# xe.net
KiCad netlist of a schematic drawn in Altium Designer
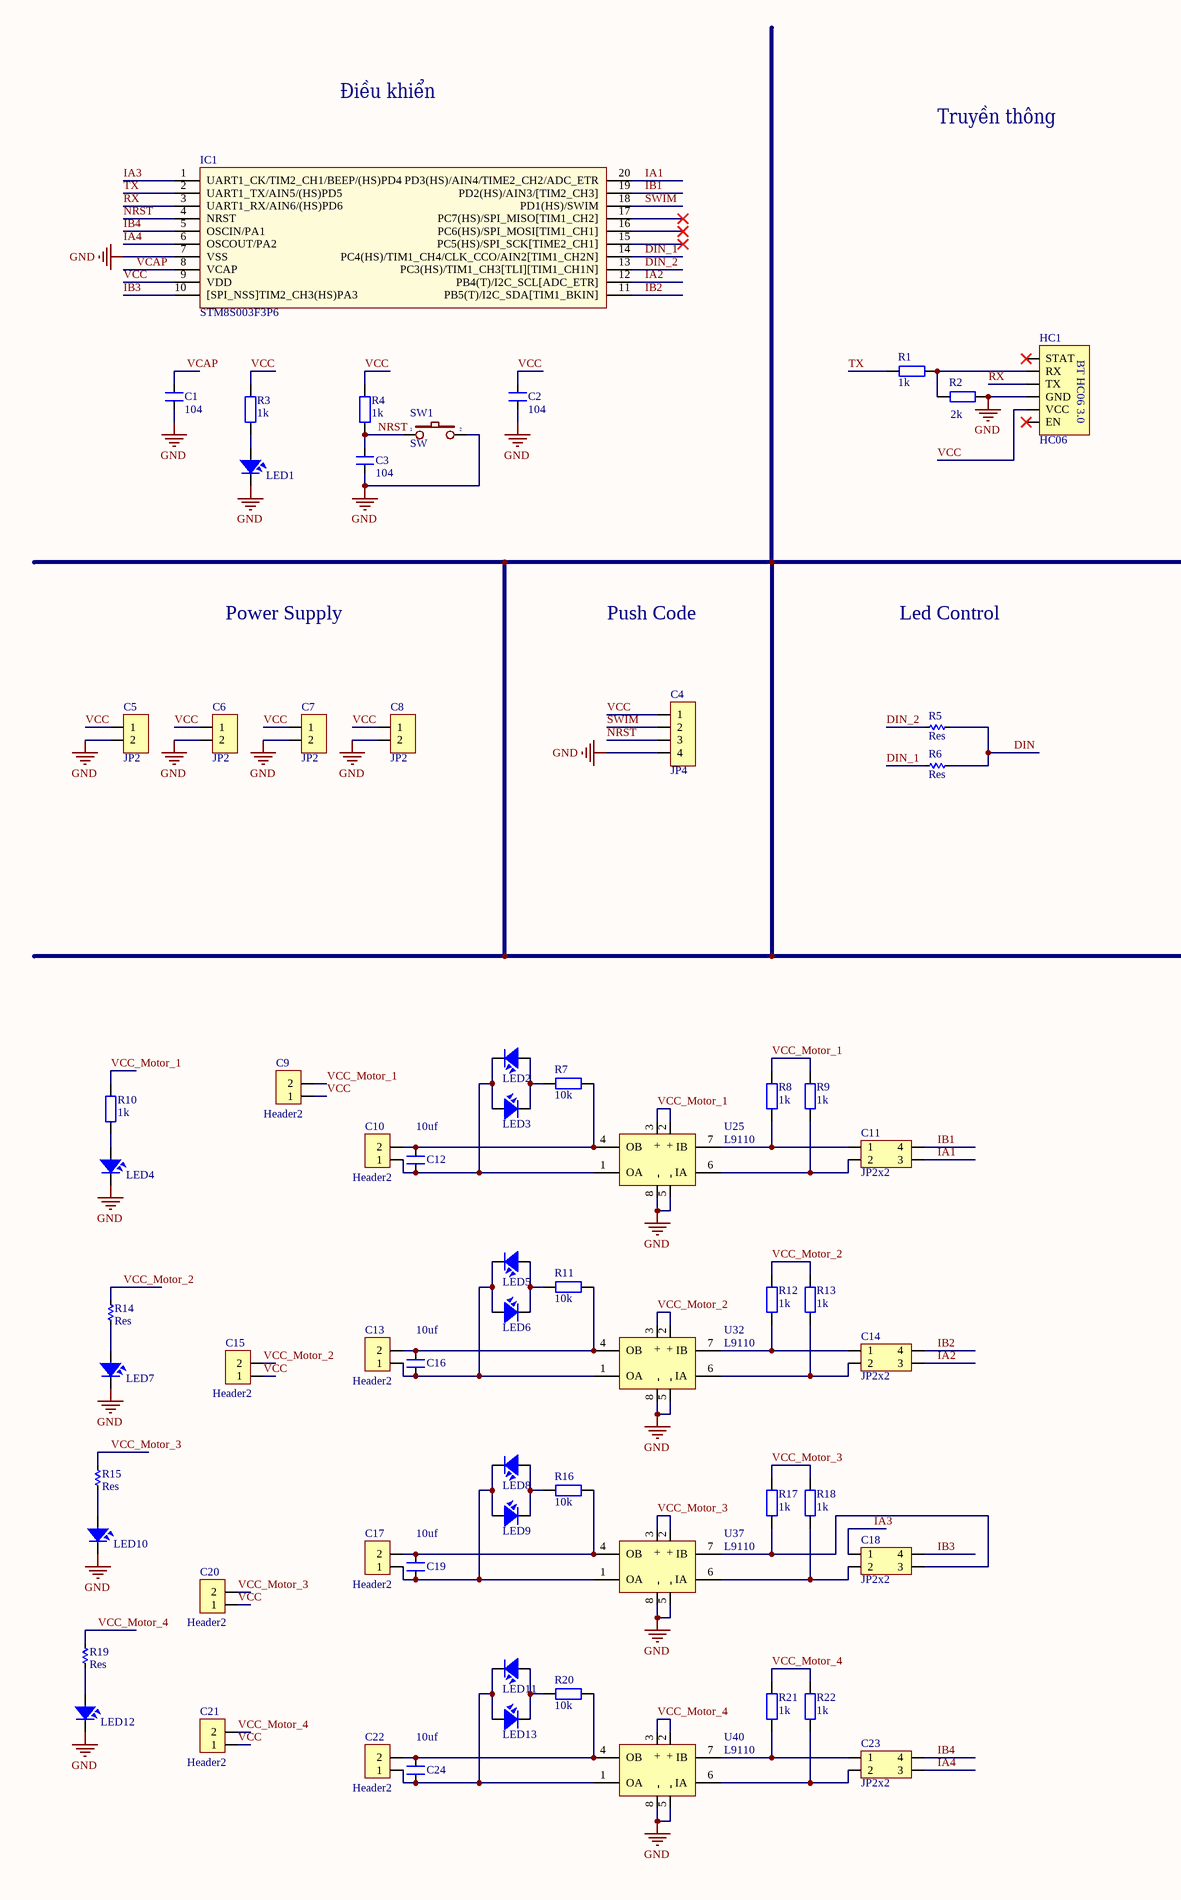
[diagram p0: xe.SchDoc, left]
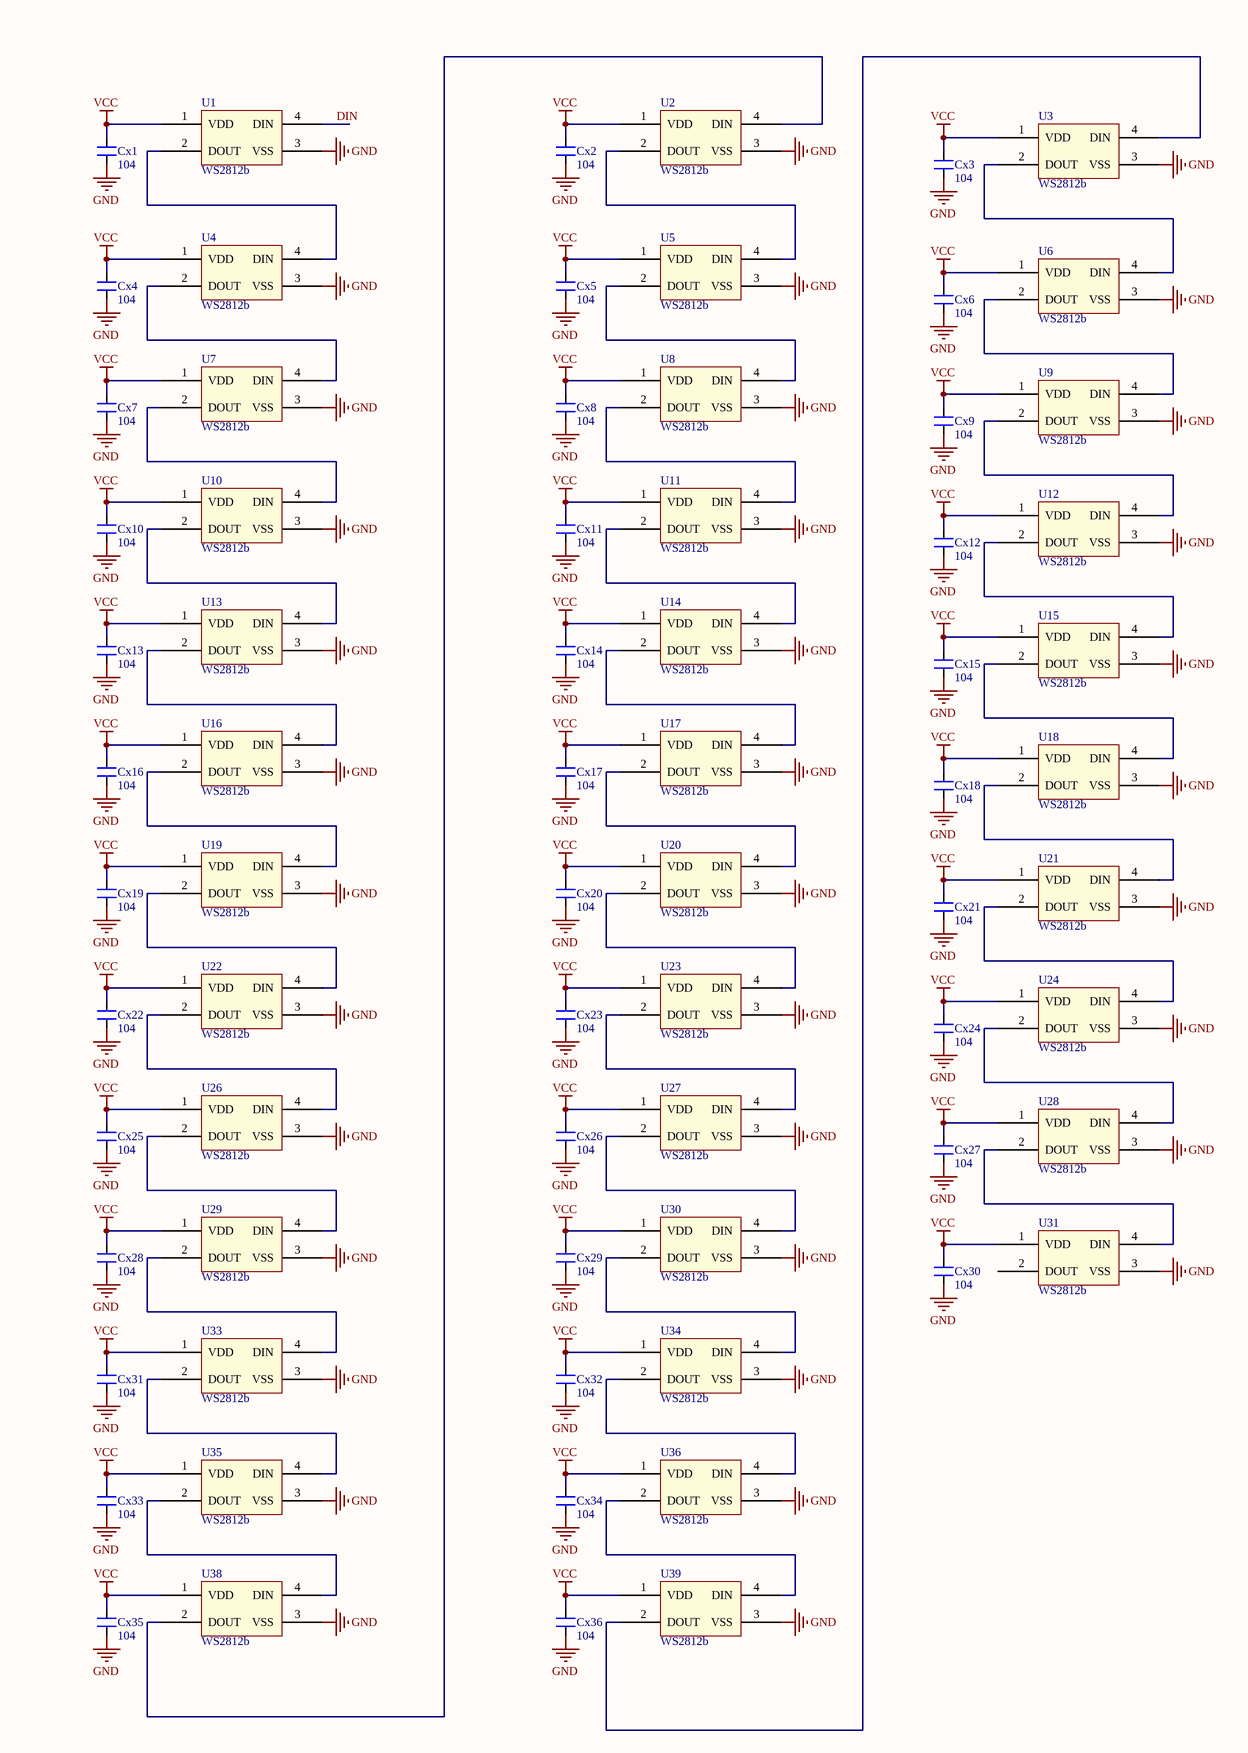
[diagram p1: xe.SchDoc, right]

(export (version "E")
  (design (tool "Eeschema 10.0.6"))
  (components
    (comp (ref "C1")
      (value "104")
      (footprint "SM-CAP-0805")
      (fields (field (name "DESIGNED BY") "VanDungEvn"))
      (libsource (lib "syhaunguyen") (part "CN"))
    )
    (comp (ref "C2")
      (value "104")
      (footprint "SM-CAP-0805")
      (fields (field (name "DESIGNED BY") "VanDungEvn"))
      (libsource (lib "syhaunguyen") (part "CN"))
    )
    (comp (ref "C3")
      (value "104")
      (footprint "SM-CAP-0805")
      (fields (field (name "DESIGNED BY") "VanDungEvn"))
      (libsource (lib "syhaunguyen") (part "CN"))
    )
    (comp (ref "C4")
      (value "JP4")
      (footprint "JP4-D1C")
      (description "WR-PHD 2.54 mm Angled Socket Header")
      (fields
        (field (name "MANUFACTURER") "Würth Elektronik eiSos GmbH")
        (field (name "PARTNO") "613004143121")
        (field (name "CREATED BY") "Karrer Zheng")
      )
      (libsource (lib "LIBRARY") (part "JP4"))
    )
    (comp (ref "C5")
      (value "JP2")
      (footprint "JP2-C1T")
      (description "WR-PHD 2.54 mm Angled Socket Header")
      (fields
        (field (name "MANUFACTURER") "Würth Elektronik eiSos GmbH")
        (field (name "PARTNO") "613002143121")
        (field (name "CREATED BY") "Karrer Zheng")
      )
      (libsource (lib "LIBRARY") (part "JP2"))
    )
    (comp (ref "C6")
      (value "JP2")
      (footprint "JP2-C1T")
      (description "WR-PHD 2.54 mm Angled Socket Header")
      (fields
        (field (name "MANUFACTURER") "Würth Elektronik eiSos GmbH")
        (field (name "PARTNO") "613002143121")
        (field (name "CREATED BY") "Karrer Zheng")
      )
      (libsource (lib "LIBRARY") (part "JP2"))
    )
    (comp (ref "C7")
      (value "JP2")
      (footprint "JP2-C1T")
      (description "WR-PHD 2.54 mm Angled Socket Header")
      (fields
        (field (name "MANUFACTURER") "Würth Elektronik eiSos GmbH")
        (field (name "PARTNO") "613002143121")
        (field (name "CREATED BY") "Karrer Zheng")
      )
      (libsource (lib "LIBRARY") (part "JP2"))
    )
    (comp (ref "C8")
      (value "JP2")
      (footprint "JP2-C1T")
      (description "WR-PHD 2.54 mm Angled Socket Header")
      (fields
        (field (name "MANUFACTURER") "Würth Elektronik eiSos GmbH")
        (field (name "PARTNO") "613002143121")
        (field (name "CREATED BY") "Karrer Zheng")
      )
      (libsource (lib "LIBRARY") (part "JP2"))
    )
    (comp (ref "C9")
      (value "Header2")
      (footprint "Header2")
      (description "Header IDC, 2 x 1 Pin Vertical 2.54mm Pitch (Non-Boxed, Male)")
      (fields
        (field (name "MANUFACTURER") "Würth Elektronik eiSos GmbH")
        (field (name "PARTNO") "613002143121")
        (field (name "CREATED BY") "Karrer Zheng")
      )
      (libsource (lib "LIBRARY") (part "Header2"))
    )
    (comp (ref "C10")
      (value "Header2")
      (footprint "Header2")
      (description "Header IDC, 2 x 1 Pin Vertical 2.54mm Pitch (Non-Boxed, Male)")
      (fields
        (field (name "MANUFACTURER") "Würth Elektronik eiSos GmbH")
        (field (name "PARTNO") "613002143121")
        (field (name "CREATED BY") "Karrer Zheng")
      )
      (libsource (lib "LIBRARY") (part "Header2"))
    )
    (comp (ref "C11")
      (value "JP2x2")
      (footprint "JP2-D2T")
      (description "WR-PHD 2.54 mm Dual Socket Header")
      (fields
        (field (name "MANUFACTURER") "Würth Elektronik eiSos GmbH")
        (field (name "PARTNO") "61300421821")
        (field (name "CREATED BY") "Karrer Zheng")
      )
      (libsource (lib "LIBRARY") (part "JP2x2"))
    )
    (comp (ref "C12")
      (value "10uf")
      (footprint "SM-CAP-0805")
      (fields (field (name "DESIGNED BY") "VanDungEvn"))
      (libsource (lib "syhaunguyen") (part "CN"))
    )
    (comp (ref "C13")
      (value "Header2")
      (footprint "Header2")
      (description "Header IDC, 2 x 1 Pin Vertical 2.54mm Pitch (Non-Boxed, Male)")
      (fields
        (field (name "MANUFACTURER") "Würth Elektronik eiSos GmbH")
        (field (name "PARTNO") "613002143121")
        (field (name "CREATED BY") "Karrer Zheng")
      )
      (libsource (lib "LIBRARY") (part "Header2"))
    )
    (comp (ref "C14")
      (value "JP2x2")
      (footprint "JP2-D2T")
      (description "WR-PHD 2.54 mm Dual Socket Header")
      (fields
        (field (name "MANUFACTURER") "Würth Elektronik eiSos GmbH")
        (field (name "PARTNO") "61300421821")
        (field (name "CREATED BY") "Karrer Zheng")
      )
      (libsource (lib "LIBRARY") (part "JP2x2"))
    )
    (comp (ref "C15")
      (value "Header2")
      (footprint "Header2")
      (description "Header IDC, 2 x 1 Pin Vertical 2.54mm Pitch (Non-Boxed, Male)")
      (fields
        (field (name "MANUFACTURER") "Würth Elektronik eiSos GmbH")
        (field (name "PARTNO") "613002143121")
        (field (name "CREATED BY") "Karrer Zheng")
      )
      (libsource (lib "LIBRARY") (part "Header2"))
    )
    (comp (ref "C16")
      (value "10uf")
      (footprint "SM-CAP-0805")
      (fields (field (name "DESIGNED BY") "VanDungEvn"))
      (libsource (lib "syhaunguyen") (part "CN"))
    )
    (comp (ref "C17")
      (value "Header2")
      (footprint "Header2")
      (description "Header IDC, 2 x 1 Pin Vertical 2.54mm Pitch (Non-Boxed, Male)")
      (fields
        (field (name "MANUFACTURER") "Würth Elektronik eiSos GmbH")
        (field (name "PARTNO") "613002143121")
        (field (name "CREATED BY") "Karrer Zheng")
      )
      (libsource (lib "LIBRARY") (part "Header2"))
    )
    (comp (ref "C18")
      (value "JP2x2")
      (footprint "JP2-D2T")
      (description "WR-PHD 2.54 mm Dual Socket Header")
      (fields
        (field (name "MANUFACTURER") "Würth Elektronik eiSos GmbH")
        (field (name "PARTNO") "61300421821")
        (field (name "CREATED BY") "Karrer Zheng")
      )
      (libsource (lib "LIBRARY") (part "JP2x2"))
    )
    (comp (ref "C19")
      (value "10uf")
      (footprint "SM-CAP-0805")
      (fields (field (name "DESIGNED BY") "VanDungEvn"))
      (libsource (lib "syhaunguyen") (part "CN"))
    )
    (comp (ref "C20")
      (value "Header2")
      (footprint "Header2")
      (description "Header IDC, 2 x 1 Pin Vertical 2.54mm Pitch (Non-Boxed, Male)")
      (fields
        (field (name "MANUFACTURER") "Würth Elektronik eiSos GmbH")
        (field (name "PARTNO") "613002143121")
        (field (name "CREATED BY") "Karrer Zheng")
      )
      (libsource (lib "LIBRARY") (part "Header2"))
    )
    (comp (ref "C21")
      (value "Header2")
      (footprint "Header2")
      (description "Header IDC, 2 x 1 Pin Vertical 2.54mm Pitch (Non-Boxed, Male)")
      (fields
        (field (name "MANUFACTURER") "Würth Elektronik eiSos GmbH")
        (field (name "PARTNO") "613002143121")
        (field (name "CREATED BY") "Karrer Zheng")
      )
      (libsource (lib "LIBRARY") (part "Header2"))
    )
    (comp (ref "C22")
      (value "Header2")
      (footprint "Header2")
      (description "Header IDC, 2 x 1 Pin Vertical 2.54mm Pitch (Non-Boxed, Male)")
      (fields
        (field (name "MANUFACTURER") "Würth Elektronik eiSos GmbH")
        (field (name "PARTNO") "613002143121")
        (field (name "CREATED BY") "Karrer Zheng")
      )
      (libsource (lib "LIBRARY") (part "Header2"))
    )
    (comp (ref "C23")
      (value "JP2x2")
      (footprint "JP2-D2T")
      (description "WR-PHD 2.54 mm Dual Socket Header")
      (fields
        (field (name "MANUFACTURER") "Würth Elektronik eiSos GmbH")
        (field (name "PARTNO") "61300421821")
        (field (name "CREATED BY") "Karrer Zheng")
      )
      (libsource (lib "LIBRARY") (part "JP2x2"))
    )
    (comp (ref "C24")
      (value "10uf")
      (footprint "SM-CAP-0805")
      (fields (field (name "DESIGNED BY") "VanDungEvn"))
      (libsource (lib "syhaunguyen") (part "CN"))
    )
    (comp (ref "Cx1") (value "104") (footprint "CN-SMD-0805") (libsource (lib "LIBRARY") (part "CN")))
    (comp (ref "Cx2") (value "104") (footprint "CN-SMD-0805") (libsource (lib "LIBRARY") (part "CN")))
    (comp (ref "Cx3") (value "104") (footprint "CN-SMD-0805") (libsource (lib "LIBRARY") (part "CN")))
    (comp (ref "Cx4") (value "104") (footprint "CN-SMD-0805") (libsource (lib "LIBRARY") (part "CN")))
    (comp (ref "Cx5") (value "104") (footprint "CN-SMD-0805") (libsource (lib "LIBRARY") (part "CN")))
    (comp (ref "Cx6") (value "104") (footprint "CN-SMD-0805") (libsource (lib "LIBRARY") (part "CN")))
    (comp (ref "Cx7") (value "104") (footprint "CN-SMD-0805") (libsource (lib "LIBRARY") (part "CN")))
    (comp (ref "Cx8") (value "104") (footprint "CN-SMD-0805") (libsource (lib "LIBRARY") (part "CN")))
    (comp (ref "Cx9") (value "104") (footprint "CN-SMD-0805") (libsource (lib "LIBRARY") (part "CN")))
    (comp (ref "Cx10") (value "104") (footprint "CN-SMD-0805") (libsource (lib "LIBRARY") (part "CN")))
    (comp (ref "Cx11") (value "104") (footprint "CN-SMD-0805") (libsource (lib "LIBRARY") (part "CN")))
    (comp (ref "Cx12") (value "104") (footprint "CN-SMD-0805") (libsource (lib "LIBRARY") (part "CN")))
    (comp (ref "Cx13") (value "104") (footprint "CN-SMD-0805") (libsource (lib "LIBRARY") (part "CN")))
    (comp (ref "Cx14") (value "104") (footprint "CN-SMD-0805") (libsource (lib "LIBRARY") (part "CN")))
    (comp (ref "Cx15") (value "104") (footprint "CN-SMD-0805") (libsource (lib "LIBRARY") (part "CN")))
    (comp (ref "Cx16") (value "104") (footprint "CN-SMD-0805") (libsource (lib "LIBRARY") (part "CN")))
    (comp (ref "Cx17") (value "104") (footprint "CN-SMD-0805") (libsource (lib "LIBRARY") (part "CN")))
    (comp (ref "Cx18") (value "104") (footprint "CN-SMD-0805") (libsource (lib "LIBRARY") (part "CN")))
    (comp (ref "Cx19") (value "104") (footprint "CN-SMD-0805") (libsource (lib "LIBRARY") (part "CN")))
    (comp (ref "Cx20") (value "104") (footprint "CN-SMD-0805") (libsource (lib "LIBRARY") (part "CN")))
    (comp (ref "Cx21") (value "104") (footprint "CN-SMD-0805") (libsource (lib "LIBRARY") (part "CN")))
    (comp (ref "Cx22") (value "104") (footprint "CN-SMD-0805") (libsource (lib "LIBRARY") (part "CN")))
    (comp (ref "Cx23") (value "104") (footprint "CN-SMD-0805") (libsource (lib "LIBRARY") (part "CN")))
    (comp (ref "Cx24") (value "104") (footprint "CN-SMD-0805") (libsource (lib "LIBRARY") (part "CN")))
    (comp (ref "Cx25") (value "104") (footprint "CN-SMD-0805") (libsource (lib "LIBRARY") (part "CN")))
    (comp (ref "Cx26") (value "104") (footprint "CN-SMD-0805") (libsource (lib "LIBRARY") (part "CN")))
    (comp (ref "Cx27") (value "104") (footprint "CN-SMD-0805") (libsource (lib "LIBRARY") (part "CN")))
    (comp (ref "Cx28") (value "104") (footprint "CN-SMD-0805") (libsource (lib "LIBRARY") (part "CN")))
    (comp (ref "Cx29") (value "104") (footprint "CN-SMD-0805") (libsource (lib "LIBRARY") (part "CN")))
    (comp (ref "Cx30") (value "104") (footprint "CN-SMD-0805") (libsource (lib "LIBRARY") (part "CN")))
    (comp (ref "Cx31") (value "104") (footprint "CN-SMD-0805") (libsource (lib "LIBRARY") (part "CN")))
    (comp (ref "Cx32") (value "104") (footprint "CN-SMD-0805") (libsource (lib "LIBRARY") (part "CN")))
    (comp (ref "Cx33") (value "104") (footprint "CN-SMD-0805") (libsource (lib "LIBRARY") (part "CN")))
    (comp (ref "Cx34") (value "104") (footprint "CN-SMD-0805") (libsource (lib "LIBRARY") (part "CN")))
    (comp (ref "Cx35") (value "104") (footprint "CN-SMD-0805") (libsource (lib "LIBRARY") (part "CN")))
    (comp (ref "Cx36") (value "104") (footprint "CN-SMD-0805") (libsource (lib "LIBRARY") (part "CN")))
    (comp (ref "HC1")
      (value "HC06")
      (footprint "HC06")
      (fields
        (field (name "MANUFACTURER") "Würth Elektronik eiSos GmbH")
        (field (name "PARTNO") "613004143121")
        (field (name "CREATED BY") "Karrer Zheng")
      )
      (libsource (lib "LIBRARY") (part "HC06"))
    )
    (comp (ref "IC1")
      (value "STM8S003F3P6")
      (footprint "TSSOP20")
      (description "MCU 8BIT  8KB FLASH TSSOP-20")
      (fields (field (name "COPYRIGHT BY") "VanDungEvn"))
      (libsource (lib "LIBRARY") (part "STM8S003F3P6"))
    )
    (comp (ref "LED1")
      (value "LED SMD")
      (footprint "SM-LED-0805-Green")
      (libsource (lib "syhaunguyen") (part "LED-SMD-0805"))
    )
    (comp (ref "LED2") (value "LED") (footprint "LED-0805-Red") (libsource (lib "LIBRARY") (part "LED SMD")))
    (comp (ref "LED3")
      (value "LED")
      (footprint "LED-0805-Green")
      (libsource (lib "LIBRARY") (part "LED SMD"))
    )
    (comp (ref "LED4") (value "LED") (footprint "LED-0805-Red") (libsource (lib "LIBRARY") (part "LED SMD")))
    (comp (ref "LED5") (value "LED") (footprint "LED-0805-Red") (libsource (lib "LIBRARY") (part "LED SMD")))
    (comp (ref "LED6")
      (value "LED")
      (footprint "LED-0805-Green")
      (libsource (lib "LIBRARY") (part "LED SMD"))
    )
    (comp (ref "LED7")
      (value "LED")
      (footprint "LED-0805-Green")
      (libsource (lib "LIBRARY") (part "LED SMD"))
    )
    (comp (ref "LED8") (value "LED") (footprint "LED-0805-Red") (libsource (lib "LIBRARY") (part "LED SMD")))
    (comp (ref "LED9")
      (value "LED")
      (footprint "LED-0805-Green")
      (libsource (lib "LIBRARY") (part "LED SMD"))
    )
    (comp (ref "LED10")
      (value "LED")
      (footprint "LED-0805-Green")
      (libsource (lib "LIBRARY") (part "LED SMD"))
    )
    (comp (ref "LED11") (value "LED") (footprint "LED-0805-Red") (libsource (lib "LIBRARY") (part "LED SMD")))
    (comp (ref "LED12")
      (value "LED")
      (footprint "LED-0805-Green")
      (libsource (lib "LIBRARY") (part "LED SMD"))
    )
    (comp (ref "LED13")
      (value "LED")
      (footprint "LED-0805-Green")
      (libsource (lib "LIBRARY") (part "LED SMD"))
    )
    (comp (ref "R1")
      (value "1k")
      (footprint "SM-RES-0805")
      (description "Resistor 1/4W")
      (libsource (lib "syhaunguyen") (part "R1/4W"))
    )
    (comp (ref "R2")
      (value "2k")
      (footprint "SM-RES-0805")
      (description "Resistor 1/4W")
      (libsource (lib "syhaunguyen") (part "R1/4W"))
    )
    (comp (ref "R3")
      (value "1k")
      (footprint "SM-RES-0805")
      (description "Resistor 1/4W")
      (libsource (lib "syhaunguyen") (part "R1/4W"))
    )
    (comp (ref "R4")
      (value "1k")
      (footprint "SM-RES-0805")
      (description "Resistor 1/4W")
      (libsource (lib "syhaunguyen") (part "R1/4W"))
    )
    (comp (ref "R5")
      (value "Res")
      (footprint "RES-SMD-0805")
      (description "Resistor")
      (fields
        (field (name "MANUFACTURER") "Generic Components")
        (field (name "PUBLISHER") "Altium Hobart Technology Centre")
      )
      (libsource (lib "LIBRARY") (part "Res-SMD"))
    )
    (comp (ref "R6")
      (value "Res")
      (footprint "RES-SMD-0805")
      (description "Resistor")
      (fields
        (field (name "MANUFACTURER") "Generic Components")
        (field (name "PUBLISHER") "Altium Hobart Technology Centre")
      )
      (libsource (lib "LIBRARY") (part "Res-SMD"))
    )
    (comp (ref "R7")
      (value "10k")
      (footprint "SM-RES-0805")
      (description "Resistor 1/4W")
      (libsource (lib "syhaunguyen") (part "R1/4W"))
    )
    (comp (ref "R8")
      (value "1k")
      (footprint "SM-RES-0805")
      (description "Resistor 1/4W")
      (libsource (lib "syhaunguyen") (part "R1/4W"))
    )
    (comp (ref "R9")
      (value "1k")
      (footprint "SM-RES-0805")
      (description "Resistor 1/4W")
      (libsource (lib "syhaunguyen") (part "R1/4W"))
    )
    (comp (ref "R10")
      (value "1k")
      (footprint "SM-RES-0805")
      (description "Resistor 1/4W")
      (libsource (lib "syhaunguyen") (part "R1/4W"))
    )
    (comp (ref "R11")
      (value "10k")
      (footprint "SM-RES-0805")
      (description "Resistor 1/4W")
      (libsource (lib "syhaunguyen") (part "R1/4W"))
    )
    (comp (ref "R12")
      (value "1k")
      (footprint "SM-RES-0805")
      (description "Resistor 1/4W")
      (libsource (lib "syhaunguyen") (part "R1/4W"))
    )
    (comp (ref "R13")
      (value "1k")
      (footprint "SM-RES-0805")
      (description "Resistor 1/4W")
      (libsource (lib "syhaunguyen") (part "R1/4W"))
    )
    (comp (ref "R14")
      (value "Res")
      (footprint "RES-SMD-0805")
      (description "Resistor")
      (fields
        (field (name "MANUFACTURER") "Generic Components")
        (field (name "PUBLISHER") "Altium Hobart Technology Centre")
      )
      (libsource (lib "LIBRARY") (part "Res-SMD"))
    )
    (comp (ref "R15")
      (value "Res")
      (footprint "RES-SMD-0805")
      (description "Resistor")
      (fields
        (field (name "MANUFACTURER") "Generic Components")
        (field (name "PUBLISHER") "Altium Hobart Technology Centre")
      )
      (libsource (lib "LIBRARY") (part "Res-SMD"))
    )
    (comp (ref "R16")
      (value "10k")
      (footprint "SM-RES-0805")
      (description "Resistor 1/4W")
      (libsource (lib "syhaunguyen") (part "R1/4W"))
    )
    (comp (ref "R17")
      (value "1k")
      (footprint "SM-RES-0805")
      (description "Resistor 1/4W")
      (libsource (lib "syhaunguyen") (part "R1/4W"))
    )
    (comp (ref "R18")
      (value "1k")
      (footprint "SM-RES-0805")
      (description "Resistor 1/4W")
      (libsource (lib "syhaunguyen") (part "R1/4W"))
    )
    (comp (ref "R19")
      (value "Res")
      (footprint "RES-SMD-0805")
      (description "Resistor")
      (fields
        (field (name "MANUFACTURER") "Generic Components")
        (field (name "PUBLISHER") "Altium Hobart Technology Centre")
      )
      (libsource (lib "LIBRARY") (part "Res-SMD"))
    )
    (comp (ref "R20")
      (value "10k")
      (footprint "SM-RES-0805")
      (description "Resistor 1/4W")
      (libsource (lib "syhaunguyen") (part "R1/4W"))
    )
    (comp (ref "R21")
      (value "1k")
      (footprint "SM-RES-0805")
      (description "Resistor 1/4W")
      (libsource (lib "syhaunguyen") (part "R1/4W"))
    )
    (comp (ref "R22")
      (value "1k")
      (footprint "SM-RES-0805")
      (description "Resistor 1/4W")
      (libsource (lib "syhaunguyen") (part "R1/4W"))
    )
    (comp (ref "SW1")
      (value "SW")
      (footprint "SW1-SMD")
      (description "Switch button 2 pin")
      (libsource (lib "LIBRARY") (part "SW2"))
    )
    (comp (ref "U1")
      (value "WS2812b")
      (footprint "PCBComponent_1 - duplicate")
      (libsource (lib "ws2812b") (part "WS2812b"))
    )
    (comp (ref "U2")
      (value "WS2812b")
      (footprint "PCBComponent_1 - duplicate")
      (libsource (lib "ws2812b") (part "WS2812b"))
    )
    (comp (ref "U3")
      (value "WS2812b")
      (footprint "PCBComponent_1 - duplicate")
      (libsource (lib "ws2812b") (part "WS2812b"))
    )
    (comp (ref "U4")
      (value "WS2812b")
      (footprint "PCBComponent_1 - duplicate")
      (libsource (lib "ws2812b") (part "WS2812b"))
    )
    (comp (ref "U5")
      (value "WS2812b")
      (footprint "PCBComponent_1 - duplicate")
      (libsource (lib "ws2812b") (part "WS2812b"))
    )
    (comp (ref "U6")
      (value "WS2812b")
      (footprint "PCBComponent_1 - duplicate")
      (libsource (lib "ws2812b") (part "WS2812b"))
    )
    (comp (ref "U7")
      (value "WS2812b")
      (footprint "PCBComponent_1 - duplicate")
      (libsource (lib "ws2812b") (part "WS2812b"))
    )
    (comp (ref "U8")
      (value "WS2812b")
      (footprint "PCBComponent_1 - duplicate")
      (libsource (lib "ws2812b") (part "WS2812b"))
    )
    (comp (ref "U9")
      (value "WS2812b")
      (footprint "PCBComponent_1 - duplicate")
      (libsource (lib "ws2812b") (part "WS2812b"))
    )
    (comp (ref "U10")
      (value "WS2812b")
      (footprint "PCBComponent_1 - duplicate")
      (libsource (lib "ws2812b") (part "WS2812b"))
    )
    (comp (ref "U11")
      (value "WS2812b")
      (footprint "PCBComponent_1 - duplicate")
      (libsource (lib "ws2812b") (part "WS2812b"))
    )
    (comp (ref "U12")
      (value "WS2812b")
      (footprint "PCBComponent_1 - duplicate")
      (libsource (lib "ws2812b") (part "WS2812b"))
    )
    (comp (ref "U13")
      (value "WS2812b")
      (footprint "PCBComponent_1 - duplicate")
      (libsource (lib "ws2812b") (part "WS2812b"))
    )
    (comp (ref "U14")
      (value "WS2812b")
      (footprint "PCBComponent_1 - duplicate")
      (libsource (lib "ws2812b") (part "WS2812b"))
    )
    (comp (ref "U15")
      (value "WS2812b")
      (footprint "PCBComponent_1 - duplicate")
      (libsource (lib "ws2812b") (part "WS2812b"))
    )
    (comp (ref "U16")
      (value "WS2812b")
      (footprint "PCBComponent_1 - duplicate")
      (libsource (lib "ws2812b") (part "WS2812b"))
    )
    (comp (ref "U17")
      (value "WS2812b")
      (footprint "PCBComponent_1 - duplicate")
      (libsource (lib "ws2812b") (part "WS2812b"))
    )
    (comp (ref "U18")
      (value "WS2812b")
      (footprint "PCBComponent_1 - duplicate")
      (libsource (lib "ws2812b") (part "WS2812b"))
    )
    (comp (ref "U19")
      (value "WS2812b")
      (footprint "PCBComponent_1 - duplicate")
      (libsource (lib "ws2812b") (part "WS2812b"))
    )
    (comp (ref "U20")
      (value "WS2812b")
      (footprint "PCBComponent_1 - duplicate")
      (libsource (lib "ws2812b") (part "WS2812b"))
    )
    (comp (ref "U21")
      (value "WS2812b")
      (footprint "PCBComponent_1 - duplicate")
      (libsource (lib "ws2812b") (part "WS2812b"))
    )
    (comp (ref "U22")
      (value "WS2812b")
      (footprint "PCBComponent_1 - duplicate")
      (libsource (lib "ws2812b") (part "WS2812b"))
    )
    (comp (ref "U23")
      (value "WS2812b")
      (footprint "PCBComponent_1 - duplicate")
      (libsource (lib "ws2812b") (part "WS2812b"))
    )
    (comp (ref "U24")
      (value "WS2812b")
      (footprint "PCBComponent_1 - duplicate")
      (libsource (lib "ws2812b") (part "WS2812b"))
    )
    (comp (ref "U25")
      (value "L9110")
      (footprint "SO8")
      (description "Half-Bridge Driver")
      (libsource (lib "LIBRARY") (part "L9110"))
    )
    (comp (ref "U26")
      (value "WS2812b")
      (footprint "PCBComponent_1 - duplicate")
      (libsource (lib "ws2812b") (part "WS2812b"))
    )
    (comp (ref "U27")
      (value "WS2812b")
      (footprint "PCBComponent_1 - duplicate")
      (libsource (lib "ws2812b") (part "WS2812b"))
    )
    (comp (ref "U28")
      (value "WS2812b")
      (footprint "PCBComponent_1 - duplicate")
      (libsource (lib "ws2812b") (part "WS2812b"))
    )
    (comp (ref "U29")
      (value "WS2812b")
      (footprint "PCBComponent_1 - duplicate")
      (libsource (lib "ws2812b") (part "WS2812b"))
    )
    (comp (ref "U30")
      (value "WS2812b")
      (footprint "PCBComponent_1 - duplicate")
      (libsource (lib "ws2812b") (part "WS2812b"))
    )
    (comp (ref "U31")
      (value "WS2812b")
      (footprint "PCBComponent_1 - duplicate")
      (libsource (lib "ws2812b") (part "WS2812b"))
    )
    (comp (ref "U32")
      (value "L9110")
      (footprint "SO8")
      (description "Half-Bridge Driver")
      (libsource (lib "LIBRARY") (part "L9110"))
    )
    (comp (ref "U33")
      (value "WS2812b")
      (footprint "PCBComponent_1 - duplicate")
      (libsource (lib "ws2812b") (part "WS2812b"))
    )
    (comp (ref "U34")
      (value "WS2812b")
      (footprint "PCBComponent_1 - duplicate")
      (libsource (lib "ws2812b") (part "WS2812b"))
    )
    (comp (ref "U35")
      (value "WS2812b")
      (footprint "PCBComponent_1 - duplicate")
      (libsource (lib "ws2812b") (part "WS2812b"))
    )
    (comp (ref "U36")
      (value "WS2812b")
      (footprint "PCBComponent_1 - duplicate")
      (libsource (lib "ws2812b") (part "WS2812b"))
    )
    (comp (ref "U37")
      (value "L9110")
      (footprint "SO8")
      (description "Half-Bridge Driver")
      (libsource (lib "LIBRARY") (part "L9110"))
    )
    (comp (ref "U38")
      (value "WS2812b")
      (footprint "PCBComponent_1 - duplicate")
      (libsource (lib "ws2812b") (part "WS2812b"))
    )
    (comp (ref "U39")
      (value "WS2812b")
      (footprint "PCBComponent_1 - duplicate")
      (libsource (lib "ws2812b") (part "WS2812b"))
    )
    (comp (ref "U40")
      (value "L9110")
      (footprint "SO8")
      (description "Half-Bridge Driver")
      (libsource (lib "LIBRARY") (part "L9110"))
    )
  )
  (nets
    (net (code "1") (name "/DIN") (class "Default")
      (node (ref "R5") (pin "2") (pinfunction "2_2") (pintype "passive"))
      (node (ref "R6") (pin "2") (pinfunction "2_2") (pintype "passive"))
      (node (ref "U1") (pin "4") (pinfunction "DIN_4") (pintype "passive"))
    )
    (net (code "2") (name "/DIN_1") (class "Default")
      (node (ref "IC1") (pin "14") (pinfunction "PC4(HS)/TIM1_CH4/CLK_CCO/AIN2[TIM1_CH2N]_14") (pintype "passive"))
      (node (ref "R6") (pin "1") (pinfunction "1_1") (pintype "passive"))
    )
    (net (code "3") (name "/DIN_2") (class "Default")
      (node (ref "IC1") (pin "13") (pinfunction "PC3(HS)/TIM1_CH3[TLI][TIM1_CH1N]_13") (pintype "passive"))
      (node (ref "R5") (pin "1") (pinfunction "1_1") (pintype "passive"))
    )
    (net (code "4") (name "/IA1") (class "Default")
      (node (ref "C11") (pin "3") (pinfunction "3_3") (pintype "passive"))
      (node (ref "IC1") (pin "20") (pinfunction "PD3(HS)/AIN4/TIME2_CH2/ADC_ETR_20") (pintype "passive"))
    )
    (net (code "5") (name "/IA2") (class "Default")
      (node (ref "C14") (pin "3") (pinfunction "3_3") (pintype "passive"))
      (node (ref "IC1") (pin "12") (pinfunction "PB4(T)/I2C_SCL[ADC_ETR]_12") (pintype "passive"))
    )
    (net (code "6") (name "/IA3") (class "Default")
      (node (ref "C18") (pin "1") (pinfunction "1_1") (pintype "passive"))
      (node (ref "IC1") (pin "1") (pinfunction "UART1_CK/TIM2_CH1/BEEP/(HS)PD4_1") (pintype "passive"))
    )
    (net (code "7") (name "/IA4") (class "Default")
      (node (ref "C23") (pin "3") (pinfunction "3_3") (pintype "passive"))
      (node (ref "IC1") (pin "6") (pinfunction "OSCOUT/PA2_6") (pintype "passive"))
    )
    (net (code "8") (name "/IB1") (class "Default")
      (node (ref "C11") (pin "4") (pinfunction "4_4") (pintype "passive"))
      (node (ref "IC1") (pin "19") (pinfunction "PD2(HS)/AIN3/[TIM2_CH3]_19") (pintype "passive"))
    )
    (net (code "9") (name "/IB2") (class "Default")
      (node (ref "C14") (pin "4") (pinfunction "4_4") (pintype "passive"))
      (node (ref "IC1") (pin "11") (pinfunction "PB5(T)/I2C_SDA[TIM1_BKIN]_11") (pintype "passive"))
    )
    (net (code "10") (name "/IB3") (class "Default")
      (node (ref "C18") (pin "4") (pinfunction "4_4") (pintype "passive"))
      (node (ref "IC1") (pin "10") (pinfunction "[SPI_NSS]TIM2_CH3(HS)PA3_10") (pintype "passive"))
    )
    (net (code "11") (name "/IB4") (class "Default")
      (node (ref "C23") (pin "4") (pinfunction "4_4") (pintype "passive"))
      (node (ref "IC1") (pin "5") (pinfunction "OSCIN/PA1_5") (pintype "passive"))
    )
    (net (code "12") (name "/NRST") (class "Default")
      (node (ref "C3") (pin "2") (pinfunction "2_2") (pintype "passive"))
      (node (ref "C4") (pin "3") (pinfunction "3_3") (pintype "passive"))
      (node (ref "IC1") (pin "4") (pinfunction "NRST_4") (pintype "passive"))
      (node (ref "R4") (pin "1") (pinfunction "1_1") (pintype "passive"))
      (node (ref "SW1") (pin "1") (pinfunction "1_1") (pintype "passive"))
    )
    (net (code "13") (name "/RX") (class "Default")
      (node (ref "HC1") (pin "3") (pinfunction "TX_3") (pintype "passive"))
      (node (ref "IC1") (pin "3") (pinfunction "UART1_RX/AIN6/(HS)PD6_3") (pintype "passive"))
    )
    (net (code "14") (name "/SWIM") (class "Default")
      (node (ref "C4") (pin "2") (pinfunction "2_2") (pintype "passive"))
      (node (ref "IC1") (pin "18") (pinfunction "PD1(HS)/SWIM_18") (pintype "passive"))
    )
    (net (code "15") (name "/TX") (class "Default")
      (node (ref "IC1") (pin "2") (pinfunction "UART1_TX/AIN5/(HS)PD5_2") (pintype "passive"))
      (node (ref "R1") (pin "2") (pinfunction "2_2") (pintype "passive"))
    )
    (net (code "16") (name "/VCAP") (class "Default")
      (node (ref "C1") (pin "2") (pinfunction "2_2") (pintype "passive"))
      (node (ref "IC1") (pin "8") (pinfunction "VCAP_8") (pintype "passive"))
    )
    (net (code "17") (name "/VCC_Motor_1") (class "Default")
      (node (ref "C9") (pin "2") (pinfunction "2_2") (pintype "passive"))
      (node (ref "R10") (pin "1") (pinfunction "1_1") (pintype "passive"))
      (node (ref "R8") (pin "2") (pinfunction "2_2") (pintype "passive"))
      (node (ref "R9") (pin "2") (pinfunction "2_2") (pintype "passive"))
      (node (ref "U25") (pin "2") (pinfunction "+_2") (pintype "passive"))
      (node (ref "U25") (pin "3") (pinfunction "+_3") (pintype "passive"))
    )
    (net (code "18") (name "/VCC_Motor_2") (class "Default")
      (node (ref "C15") (pin "2") (pinfunction "2_2") (pintype "passive"))
      (node (ref "R12") (pin "2") (pinfunction "2_2") (pintype "passive"))
      (node (ref "R13") (pin "2") (pinfunction "2_2") (pintype "passive"))
      (node (ref "R14") (pin "1") (pinfunction "1_1") (pintype "passive"))
      (node (ref "U32") (pin "2") (pinfunction "+_2") (pintype "passive"))
      (node (ref "U32") (pin "3") (pinfunction "+_3") (pintype "passive"))
    )
    (net (code "19") (name "/VCC_Motor_3") (class "Default")
      (node (ref "C20") (pin "2") (pinfunction "2_2") (pintype "passive"))
      (node (ref "R15") (pin "1") (pinfunction "1_1") (pintype "passive"))
      (node (ref "R17") (pin "2") (pinfunction "2_2") (pintype "passive"))
      (node (ref "R18") (pin "2") (pinfunction "2_2") (pintype "passive"))
      (node (ref "U37") (pin "2") (pinfunction "+_2") (pintype "passive"))
      (node (ref "U37") (pin "3") (pinfunction "+_3") (pintype "passive"))
    )
    (net (code "20") (name "/VCC_Motor_4") (class "Default")
      (node (ref "C21") (pin "2") (pinfunction "2_2") (pintype "passive"))
      (node (ref "R19") (pin "1") (pinfunction "1_1") (pintype "passive"))
      (node (ref "R21") (pin "2") (pinfunction "2_2") (pintype "passive"))
      (node (ref "R22") (pin "2") (pinfunction "2_2") (pintype "passive"))
      (node (ref "U40") (pin "2") (pinfunction "+_2") (pintype "passive"))
      (node (ref "U40") (pin "3") (pinfunction "+_3") (pintype "passive"))
    )
    (net (code "21") (name "GND") (class "Default")
      (node (ref "C1") (pin "1") (pinfunction "1_1") (pintype "passive"))
      (node (ref "C2") (pin "1") (pinfunction "1_1") (pintype "passive"))
      (node (ref "C3") (pin "1") (pinfunction "1_1") (pintype "passive"))
      (node (ref "C4") (pin "4") (pinfunction "4_4") (pintype "passive"))
      (node (ref "C5") (pin "2") (pinfunction "2_2") (pintype "passive"))
      (node (ref "C6") (pin "2") (pinfunction "2_2") (pintype "passive"))
      (node (ref "C7") (pin "2") (pinfunction "2_2") (pintype "passive"))
      (node (ref "C8") (pin "2") (pinfunction "2_2") (pintype "passive"))
      (node (ref "Cx1") (pin "1") (pinfunction "1_1") (pintype "passive"))
      (node (ref "Cx10") (pin "1") (pinfunction "1_1") (pintype "passive"))
      (node (ref "Cx11") (pin "1") (pinfunction "1_1") (pintype "passive"))
      (node (ref "Cx12") (pin "1") (pinfunction "1_1") (pintype "passive"))
      (node (ref "Cx13") (pin "1") (pinfunction "1_1") (pintype "passive"))
      (node (ref "Cx14") (pin "1") (pinfunction "1_1") (pintype "passive"))
      (node (ref "Cx15") (pin "1") (pinfunction "1_1") (pintype "passive"))
      (node (ref "Cx16") (pin "1") (pinfunction "1_1") (pintype "passive"))
      (node (ref "Cx17") (pin "1") (pinfunction "1_1") (pintype "passive"))
      (node (ref "Cx18") (pin "1") (pinfunction "1_1") (pintype "passive"))
      (node (ref "Cx19") (pin "1") (pinfunction "1_1") (pintype "passive"))
      (node (ref "Cx2") (pin "1") (pinfunction "1_1") (pintype "passive"))
      (node (ref "Cx20") (pin "1") (pinfunction "1_1") (pintype "passive"))
      (node (ref "Cx21") (pin "1") (pinfunction "1_1") (pintype "passive"))
      (node (ref "Cx22") (pin "1") (pinfunction "1_1") (pintype "passive"))
      (node (ref "Cx23") (pin "1") (pinfunction "1_1") (pintype "passive"))
      (node (ref "Cx24") (pin "1") (pinfunction "1_1") (pintype "passive"))
      (node (ref "Cx25") (pin "1") (pinfunction "1_1") (pintype "passive"))
      (node (ref "Cx26") (pin "1") (pinfunction "1_1") (pintype "passive"))
      (node (ref "Cx27") (pin "1") (pinfunction "1_1") (pintype "passive"))
      (node (ref "Cx28") (pin "1") (pinfunction "1_1") (pintype "passive"))
      (node (ref "Cx29") (pin "1") (pinfunction "1_1") (pintype "passive"))
      (node (ref "Cx3") (pin "1") (pinfunction "1_1") (pintype "passive"))
      (node (ref "Cx30") (pin "1") (pinfunction "1_1") (pintype "passive"))
      (node (ref "Cx31") (pin "1") (pinfunction "1_1") (pintype "passive"))
      (node (ref "Cx32") (pin "1") (pinfunction "1_1") (pintype "passive"))
      (node (ref "Cx33") (pin "1") (pinfunction "1_1") (pintype "passive"))
      (node (ref "Cx34") (pin "1") (pinfunction "1_1") (pintype "passive"))
      (node (ref "Cx35") (pin "1") (pinfunction "1_1") (pintype "passive"))
      (node (ref "Cx36") (pin "1") (pinfunction "1_1") (pintype "passive"))
      (node (ref "Cx4") (pin "1") (pinfunction "1_1") (pintype "passive"))
      (node (ref "Cx5") (pin "1") (pinfunction "1_1") (pintype "passive"))
      (node (ref "Cx6") (pin "1") (pinfunction "1_1") (pintype "passive"))
      (node (ref "Cx7") (pin "1") (pinfunction "1_1") (pintype "passive"))
      (node (ref "Cx8") (pin "1") (pinfunction "1_1") (pintype "passive"))
      (node (ref "Cx9") (pin "1") (pinfunction "1_1") (pintype "passive"))
      (node (ref "HC1") (pin "4") (pinfunction "GND_4") (pintype "passive"))
      (node (ref "IC1") (pin "7") (pinfunction "VSS_7") (pintype "passive"))
      (node (ref "LED1") (pin "2") (pinfunction "2_2") (pintype "passive"))
      (node (ref "LED10") (pin "2") (pinfunction "2_2") (pintype "passive"))
      (node (ref "LED12") (pin "2") (pinfunction "2_2") (pintype "passive"))
      (node (ref "LED4") (pin "2") (pinfunction "2_2") (pintype "passive"))
      (node (ref "LED7") (pin "2") (pinfunction "2_2") (pintype "passive"))
      (node (ref "R2") (pin "1") (pinfunction "1_1") (pintype "passive"))
      (node (ref "SW1") (pin "2") (pinfunction "2_2") (pintype "passive"))
      (node (ref "U1") (pin "3") (pinfunction "VSS_3") (pintype "passive"))
      (node (ref "U10") (pin "3") (pinfunction "VSS_3") (pintype "passive"))
      (node (ref "U11") (pin "3") (pinfunction "VSS_3") (pintype "passive"))
      (node (ref "U12") (pin "3") (pinfunction "VSS_3") (pintype "passive"))
      (node (ref "U13") (pin "3") (pinfunction "VSS_3") (pintype "passive"))
      (node (ref "U14") (pin "3") (pinfunction "VSS_3") (pintype "passive"))
      (node (ref "U15") (pin "3") (pinfunction "VSS_3") (pintype "passive"))
      (node (ref "U16") (pin "3") (pinfunction "VSS_3") (pintype "passive"))
      (node (ref "U17") (pin "3") (pinfunction "VSS_3") (pintype "passive"))
      (node (ref "U18") (pin "3") (pinfunction "VSS_3") (pintype "passive"))
      (node (ref "U19") (pin "3") (pinfunction "VSS_3") (pintype "passive"))
      (node (ref "U2") (pin "3") (pinfunction "VSS_3") (pintype "passive"))
      (node (ref "U20") (pin "3") (pinfunction "VSS_3") (pintype "passive"))
      (node (ref "U21") (pin "3") (pinfunction "VSS_3") (pintype "passive"))
      (node (ref "U22") (pin "3") (pinfunction "VSS_3") (pintype "passive"))
      (node (ref "U23") (pin "3") (pinfunction "VSS_3") (pintype "passive"))
      (node (ref "U24") (pin "3") (pinfunction "VSS_3") (pintype "passive"))
      (node (ref "U25") (pin "5") (pinfunction "-_5") (pintype "passive"))
      (node (ref "U25") (pin "8") (pinfunction "-_8") (pintype "passive"))
      (node (ref "U26") (pin "3") (pinfunction "VSS_3") (pintype "passive"))
      (node (ref "U27") (pin "3") (pinfunction "VSS_3") (pintype "passive"))
      (node (ref "U28") (pin "3") (pinfunction "VSS_3") (pintype "passive"))
      (node (ref "U29") (pin "3") (pinfunction "VSS_3") (pintype "passive"))
      (node (ref "U3") (pin "3") (pinfunction "VSS_3") (pintype "passive"))
      (node (ref "U30") (pin "3") (pinfunction "VSS_3") (pintype "passive"))
      (node (ref "U31") (pin "3") (pinfunction "VSS_3") (pintype "passive"))
      (node (ref "U32") (pin "5") (pinfunction "-_5") (pintype "passive"))
      (node (ref "U32") (pin "8") (pinfunction "-_8") (pintype "passive"))
      (node (ref "U33") (pin "3") (pinfunction "VSS_3") (pintype "passive"))
      (node (ref "U34") (pin "3") (pinfunction "VSS_3") (pintype "passive"))
      (node (ref "U35") (pin "3") (pinfunction "VSS_3") (pintype "passive"))
      (node (ref "U36") (pin "3") (pinfunction "VSS_3") (pintype "passive"))
      (node (ref "U37") (pin "5") (pinfunction "-_5") (pintype "passive"))
      (node (ref "U37") (pin "8") (pinfunction "-_8") (pintype "passive"))
      (node (ref "U38") (pin "3") (pinfunction "VSS_3") (pintype "passive"))
      (node (ref "U39") (pin "3") (pinfunction "VSS_3") (pintype "passive"))
      (node (ref "U4") (pin "3") (pinfunction "VSS_3") (pintype "passive"))
      (node (ref "U40") (pin "5") (pinfunction "-_5") (pintype "passive"))
      (node (ref "U40") (pin "8") (pinfunction "-_8") (pintype "passive"))
      (node (ref "U5") (pin "3") (pinfunction "VSS_3") (pintype "passive"))
      (node (ref "U6") (pin "3") (pinfunction "VSS_3") (pintype "passive"))
      (node (ref "U7") (pin "3") (pinfunction "VSS_3") (pintype "passive"))
      (node (ref "U8") (pin "3") (pinfunction "VSS_3") (pintype "passive"))
      (node (ref "U9") (pin "3") (pinfunction "VSS_3") (pintype "passive"))
    )
    (net (code "22") (name "Net-(HC1-RX)") (class "Default")
      (node (ref "HC1") (pin "2") (pinfunction "RX_2") (pintype "passive"))
      (node (ref "R1") (pin "1") (pinfunction "1_1") (pintype "passive"))
      (node (ref "R2") (pin "2") (pinfunction "2_2") (pintype "passive"))
    )
    (net (code "23") (name "Net-(LED1-Pad1)") (class "Default")
      (node (ref "LED1") (pin "1") (pinfunction "1_1") (pintype "passive"))
      (node (ref "R3") (pin "1") (pinfunction "1_1") (pintype "passive"))
    )
    (net (code "24") (name "Net-(LED2-Pad1)") (class "Default")
      (node (ref "LED2") (pin "1") (pinfunction "1_1") (pintype "passive"))
      (node (ref "LED3") (pin "2") (pinfunction "2_2") (pintype "passive"))
      (node (ref "R7") (pin "2") (pinfunction "2_2") (pintype "passive"))
    )
    (net (code "25") (name "Net-(LED4-Pad1)") (class "Default")
      (node (ref "LED4") (pin "1") (pinfunction "1_1") (pintype "passive"))
      (node (ref "R10") (pin "2") (pinfunction "2_2") (pintype "passive"))
    )
    (net (code "26") (name "Net-(LED5-Pad1)") (class "Default")
      (node (ref "LED5") (pin "1") (pinfunction "1_1") (pintype "passive"))
      (node (ref "LED6") (pin "2") (pinfunction "2_2") (pintype "passive"))
      (node (ref "R11") (pin "2") (pinfunction "2_2") (pintype "passive"))
    )
    (net (code "27") (name "Net-(LED7-Pad1)") (class "Default")
      (node (ref "LED7") (pin "1") (pinfunction "1_1") (pintype "passive"))
      (node (ref "R14") (pin "2") (pinfunction "2_2") (pintype "passive"))
    )
    (net (code "28") (name "Net-(LED8-Pad1)") (class "Default")
      (node (ref "LED8") (pin "1") (pinfunction "1_1") (pintype "passive"))
      (node (ref "LED9") (pin "2") (pinfunction "2_2") (pintype "passive"))
      (node (ref "R16") (pin "2") (pinfunction "2_2") (pintype "passive"))
    )
    (net (code "29") (name "Net-(LED10-Pad1)") (class "Default")
      (node (ref "LED10") (pin "1") (pinfunction "1_1") (pintype "passive"))
      (node (ref "R15") (pin "2") (pinfunction "2_2") (pintype "passive"))
    )
    (net (code "30") (name "Net-(LED11-Pad1)") (class "Default")
      (node (ref "LED11") (pin "1") (pinfunction "1_1") (pintype "passive"))
      (node (ref "LED13") (pin "2") (pinfunction "2_2") (pintype "passive"))
      (node (ref "R20") (pin "2") (pinfunction "2_2") (pintype "passive"))
    )
    (net (code "31") (name "Net-(LED12-Pad1)") (class "Default")
      (node (ref "LED12") (pin "1") (pinfunction "1_1") (pintype "passive"))
      (node (ref "R19") (pin "2") (pinfunction "2_2") (pintype "passive"))
    )
    (net (code "32") (name "Net-(U1-DOUT)") (class "Default")
      (node (ref "U1") (pin "2") (pinfunction "DOUT_2") (pintype "passive"))
      (node (ref "U4") (pin "4") (pinfunction "DIN_4") (pintype "passive"))
    )
    (net (code "33") (name "Net-(U2-DIN)") (class "Default")
      (node (ref "U2") (pin "4") (pinfunction "DIN_4") (pintype "passive"))
      (node (ref "U38") (pin "2") (pinfunction "DOUT_2") (pintype "passive"))
    )
    (net (code "34") (name "Net-(U2-DOUT)") (class "Default")
      (node (ref "U2") (pin "2") (pinfunction "DOUT_2") (pintype "passive"))
      (node (ref "U5") (pin "4") (pinfunction "DIN_4") (pintype "passive"))
    )
    (net (code "35") (name "Net-(U3-DIN)") (class "Default")
      (node (ref "U3") (pin "4") (pinfunction "DIN_4") (pintype "passive"))
      (node (ref "U39") (pin "2") (pinfunction "DOUT_2") (pintype "passive"))
    )
    (net (code "36") (name "Net-(U3-DOUT)") (class "Default")
      (node (ref "U3") (pin "2") (pinfunction "DOUT_2") (pintype "passive"))
      (node (ref "U6") (pin "4") (pinfunction "DIN_4") (pintype "passive"))
    )
    (net (code "37") (name "Net-(U4-DOUT)") (class "Default")
      (node (ref "U4") (pin "2") (pinfunction "DOUT_2") (pintype "passive"))
      (node (ref "U7") (pin "4") (pinfunction "DIN_4") (pintype "passive"))
    )
    (net (code "38") (name "Net-(U5-DOUT)") (class "Default")
      (node (ref "U5") (pin "2") (pinfunction "DOUT_2") (pintype "passive"))
      (node (ref "U8") (pin "4") (pinfunction "DIN_4") (pintype "passive"))
    )
    (net (code "39") (name "Net-(U6-DOUT)") (class "Default")
      (node (ref "U6") (pin "2") (pinfunction "DOUT_2") (pintype "passive"))
      (node (ref "U9") (pin "4") (pinfunction "DIN_4") (pintype "passive"))
    )
    (net (code "40") (name "Net-(U10-DIN)") (class "Default")
      (node (ref "U10") (pin "4") (pinfunction "DIN_4") (pintype "passive"))
      (node (ref "U7") (pin "2") (pinfunction "DOUT_2") (pintype "passive"))
    )
    (net (code "41") (name "Net-(U10-DOUT)") (class "Default")
      (node (ref "U10") (pin "2") (pinfunction "DOUT_2") (pintype "passive"))
      (node (ref "U13") (pin "4") (pinfunction "DIN_4") (pintype "passive"))
    )
    (net (code "42") (name "Net-(U11-DIN)") (class "Default")
      (node (ref "U11") (pin "4") (pinfunction "DIN_4") (pintype "passive"))
      (node (ref "U8") (pin "2") (pinfunction "DOUT_2") (pintype "passive"))
    )
    (net (code "43") (name "Net-(U11-DOUT)") (class "Default")
      (node (ref "U11") (pin "2") (pinfunction "DOUT_2") (pintype "passive"))
      (node (ref "U14") (pin "4") (pinfunction "DIN_4") (pintype "passive"))
    )
    (net (code "44") (name "Net-(U12-DIN)") (class "Default")
      (node (ref "U12") (pin "4") (pinfunction "DIN_4") (pintype "passive"))
      (node (ref "U9") (pin "2") (pinfunction "DOUT_2") (pintype "passive"))
    )
    (net (code "45") (name "Net-(U12-DOUT)") (class "Default")
      (node (ref "U12") (pin "2") (pinfunction "DOUT_2") (pintype "passive"))
      (node (ref "U15") (pin "4") (pinfunction "DIN_4") (pintype "passive"))
    )
    (net (code "46") (name "Net-(U13-DOUT)") (class "Default")
      (node (ref "U13") (pin "2") (pinfunction "DOUT_2") (pintype "passive"))
      (node (ref "U16") (pin "4") (pinfunction "DIN_4") (pintype "passive"))
    )
    (net (code "47") (name "Net-(U14-DOUT)") (class "Default")
      (node (ref "U14") (pin "2") (pinfunction "DOUT_2") (pintype "passive"))
      (node (ref "U17") (pin "4") (pinfunction "DIN_4") (pintype "passive"))
    )
    (net (code "48") (name "Net-(U15-DOUT)") (class "Default")
      (node (ref "U15") (pin "2") (pinfunction "DOUT_2") (pintype "passive"))
      (node (ref "U18") (pin "4") (pinfunction "DIN_4") (pintype "passive"))
    )
    (net (code "49") (name "Net-(U16-DOUT)") (class "Default")
      (node (ref "U16") (pin "2") (pinfunction "DOUT_2") (pintype "passive"))
      (node (ref "U19") (pin "4") (pinfunction "DIN_4") (pintype "passive"))
    )
    (net (code "50") (name "Net-(U17-DOUT)") (class "Default")
      (node (ref "U17") (pin "2") (pinfunction "DOUT_2") (pintype "passive"))
      (node (ref "U20") (pin "4") (pinfunction "DIN_4") (pintype "passive"))
    )
    (net (code "51") (name "Net-(U18-DOUT)") (class "Default")
      (node (ref "U18") (pin "2") (pinfunction "DOUT_2") (pintype "passive"))
      (node (ref "U21") (pin "4") (pinfunction "DIN_4") (pintype "passive"))
    )
    (net (code "52") (name "Net-(U19-DOUT)") (class "Default")
      (node (ref "U19") (pin "2") (pinfunction "DOUT_2") (pintype "passive"))
      (node (ref "U22") (pin "4") (pinfunction "DIN_4") (pintype "passive"))
    )
    (net (code "53") (name "Net-(U20-DOUT)") (class "Default")
      (node (ref "U20") (pin "2") (pinfunction "DOUT_2") (pintype "passive"))
      (node (ref "U23") (pin "4") (pinfunction "DIN_4") (pintype "passive"))
    )
    (net (code "54") (name "Net-(U21-DOUT)") (class "Default")
      (node (ref "U21") (pin "2") (pinfunction "DOUT_2") (pintype "passive"))
      (node (ref "U24") (pin "4") (pinfunction "DIN_4") (pintype "passive"))
    )
    (net (code "55") (name "Net-(U22-DOUT)") (class "Default")
      (node (ref "U22") (pin "2") (pinfunction "DOUT_2") (pintype "passive"))
      (node (ref "U26") (pin "4") (pinfunction "DIN_4") (pintype "passive"))
    )
    (net (code "56") (name "Net-(U23-DOUT)") (class "Default")
      (node (ref "U23") (pin "2") (pinfunction "DOUT_2") (pintype "passive"))
      (node (ref "U27") (pin "4") (pinfunction "DIN_4") (pintype "passive"))
    )
    (net (code "57") (name "Net-(U24-DOUT)") (class "Default")
      (node (ref "U24") (pin "2") (pinfunction "DOUT_2") (pintype "passive"))
      (node (ref "U28") (pin "4") (pinfunction "DIN_4") (pintype "passive"))
    )
    (net (code "58") (name "Net-(U25-IA)") (class "Default")
      (node (ref "C11") (pin "2") (pinfunction "2_2") (pintype "passive"))
      (node (ref "R9") (pin "1") (pinfunction "1_1") (pintype "passive"))
      (node (ref "U25") (pin "6") (pinfunction "IA_6") (pintype "passive"))
    )
    (net (code "59") (name "Net-(U25-IB)") (class "Default")
      (node (ref "C11") (pin "1") (pinfunction "1_1") (pintype "passive"))
      (node (ref "R8") (pin "1") (pinfunction "1_1") (pintype "passive"))
      (node (ref "U25") (pin "7") (pinfunction "IB_7") (pintype "passive"))
    )
    (net (code "60") (name "Net-(U25-OA)") (class "Default")
      (node (ref "C10") (pin "1") (pinfunction "1_1") (pintype "passive"))
      (node (ref "C12") (pin "1") (pinfunction "1_1") (pintype "passive"))
      (node (ref "LED2") (pin "2") (pinfunction "2_2") (pintype "passive"))
      (node (ref "LED3") (pin "1") (pinfunction "1_1") (pintype "passive"))
      (node (ref "U25") (pin "1") (pinfunction "OA_1") (pintype "passive"))
    )
    (net (code "61") (name "Net-(U25-OB)") (class "Default")
      (node (ref "C10") (pin "2") (pinfunction "2_2") (pintype "passive"))
      (node (ref "C12") (pin "2") (pinfunction "2_2") (pintype "passive"))
      (node (ref "R7") (pin "1") (pinfunction "1_1") (pintype "passive"))
      (node (ref "U25") (pin "4") (pinfunction "OB_4") (pintype "passive"))
    )
    (net (code "62") (name "Net-(U26-DOUT)") (class "Default")
      (node (ref "U26") (pin "2") (pinfunction "DOUT_2") (pintype "passive"))
      (node (ref "U29") (pin "4") (pinfunction "DIN_4") (pintype "passive"))
    )
    (net (code "63") (name "Net-(U27-DOUT)") (class "Default")
      (node (ref "U27") (pin "2") (pinfunction "DOUT_2") (pintype "passive"))
      (node (ref "U30") (pin "4") (pinfunction "DIN_4") (pintype "passive"))
    )
    (net (code "64") (name "Net-(U28-DOUT)") (class "Default")
      (node (ref "U28") (pin "2") (pinfunction "DOUT_2") (pintype "passive"))
      (node (ref "U31") (pin "4") (pinfunction "DIN_4") (pintype "passive"))
    )
    (net (code "65") (name "Net-(U29-DOUT)") (class "Default")
      (node (ref "U29") (pin "2") (pinfunction "DOUT_2") (pintype "passive"))
      (node (ref "U33") (pin "4") (pinfunction "DIN_4") (pintype "passive"))
    )
    (net (code "66") (name "Net-(U30-DOUT)") (class "Default")
      (node (ref "U30") (pin "2") (pinfunction "DOUT_2") (pintype "passive"))
      (node (ref "U34") (pin "4") (pinfunction "DIN_4") (pintype "passive"))
    )
    (net (code "67") (name "Net-(U32-IA)") (class "Default")
      (node (ref "C14") (pin "2") (pinfunction "2_2") (pintype "passive"))
      (node (ref "R13") (pin "1") (pinfunction "1_1") (pintype "passive"))
      (node (ref "U32") (pin "6") (pinfunction "IA_6") (pintype "passive"))
    )
    (net (code "68") (name "Net-(U32-IB)") (class "Default")
      (node (ref "C14") (pin "1") (pinfunction "1_1") (pintype "passive"))
      (node (ref "R12") (pin "1") (pinfunction "1_1") (pintype "passive"))
      (node (ref "U32") (pin "7") (pinfunction "IB_7") (pintype "passive"))
    )
    (net (code "69") (name "Net-(U32-OA)") (class "Default")
      (node (ref "C13") (pin "1") (pinfunction "1_1") (pintype "passive"))
      (node (ref "C16") (pin "1") (pinfunction "1_1") (pintype "passive"))
      (node (ref "LED5") (pin "2") (pinfunction "2_2") (pintype "passive"))
      (node (ref "LED6") (pin "1") (pinfunction "1_1") (pintype "passive"))
      (node (ref "U32") (pin "1") (pinfunction "OA_1") (pintype "passive"))
    )
    (net (code "70") (name "Net-(U32-OB)") (class "Default")
      (node (ref "C13") (pin "2") (pinfunction "2_2") (pintype "passive"))
      (node (ref "C16") (pin "2") (pinfunction "2_2") (pintype "passive"))
      (node (ref "R11") (pin "1") (pinfunction "1_1") (pintype "passive"))
      (node (ref "U32") (pin "4") (pinfunction "OB_4") (pintype "passive"))
    )
    (net (code "71") (name "Net-(U33-DOUT)") (class "Default")
      (node (ref "U33") (pin "2") (pinfunction "DOUT_2") (pintype "passive"))
      (node (ref "U35") (pin "4") (pinfunction "DIN_4") (pintype "passive"))
    )
    (net (code "72") (name "Net-(U34-DOUT)") (class "Default")
      (node (ref "U34") (pin "2") (pinfunction "DOUT_2") (pintype "passive"))
      (node (ref "U36") (pin "4") (pinfunction "DIN_4") (pintype "passive"))
    )
    (net (code "73") (name "Net-(U35-DOUT)") (class "Default")
      (node (ref "U35") (pin "2") (pinfunction "DOUT_2") (pintype "passive"))
      (node (ref "U38") (pin "4") (pinfunction "DIN_4") (pintype "passive"))
    )
    (net (code "74") (name "Net-(U36-DOUT)") (class "Default")
      (node (ref "U36") (pin "2") (pinfunction "DOUT_2") (pintype "passive"))
      (node (ref "U39") (pin "4") (pinfunction "DIN_4") (pintype "passive"))
    )
    (net (code "75") (name "Net-(U37-IA)") (class "Default")
      (node (ref "C18") (pin "2") (pinfunction "2_2") (pintype "passive"))
      (node (ref "R18") (pin "1") (pinfunction "1_1") (pintype "passive"))
      (node (ref "U37") (pin "6") (pinfunction "IA_6") (pintype "passive"))
    )
    (net (code "76") (name "Net-(U37-IB)") (class "Default")
      (node (ref "C18") (pin "3") (pinfunction "3_3") (pintype "passive"))
      (node (ref "R17") (pin "1") (pinfunction "1_1") (pintype "passive"))
      (node (ref "U37") (pin "7") (pinfunction "IB_7") (pintype "passive"))
    )
    (net (code "77") (name "Net-(U37-OA)") (class "Default")
      (node (ref "C17") (pin "1") (pinfunction "1_1") (pintype "passive"))
      (node (ref "C19") (pin "1") (pinfunction "1_1") (pintype "passive"))
      (node (ref "LED8") (pin "2") (pinfunction "2_2") (pintype "passive"))
      (node (ref "LED9") (pin "1") (pinfunction "1_1") (pintype "passive"))
      (node (ref "U37") (pin "1") (pinfunction "OA_1") (pintype "passive"))
    )
    (net (code "78") (name "Net-(U37-OB)") (class "Default")
      (node (ref "C17") (pin "2") (pinfunction "2_2") (pintype "passive"))
      (node (ref "C19") (pin "2") (pinfunction "2_2") (pintype "passive"))
      (node (ref "R16") (pin "1") (pinfunction "1_1") (pintype "passive"))
      (node (ref "U37") (pin "4") (pinfunction "OB_4") (pintype "passive"))
    )
    (net (code "79") (name "Net-(U40-IA)") (class "Default")
      (node (ref "C23") (pin "2") (pinfunction "2_2") (pintype "passive"))
      (node (ref "R22") (pin "1") (pinfunction "1_1") (pintype "passive"))
      (node (ref "U40") (pin "6") (pinfunction "IA_6") (pintype "passive"))
    )
    (net (code "80") (name "Net-(U40-IB)") (class "Default")
      (node (ref "C23") (pin "1") (pinfunction "1_1") (pintype "passive"))
      (node (ref "R21") (pin "1") (pinfunction "1_1") (pintype "passive"))
      (node (ref "U40") (pin "7") (pinfunction "IB_7") (pintype "passive"))
    )
    (net (code "81") (name "Net-(U40-OA)") (class "Default")
      (node (ref "C22") (pin "1") (pinfunction "1_1") (pintype "passive"))
      (node (ref "C24") (pin "1") (pinfunction "1_1") (pintype "passive"))
      (node (ref "LED11") (pin "2") (pinfunction "2_2") (pintype "passive"))
      (node (ref "LED13") (pin "1") (pinfunction "1_1") (pintype "passive"))
      (node (ref "U40") (pin "1") (pinfunction "OA_1") (pintype "passive"))
    )
    (net (code "82") (name "Net-(U40-OB)") (class "Default")
      (node (ref "C22") (pin "2") (pinfunction "2_2") (pintype "passive"))
      (node (ref "C24") (pin "2") (pinfunction "2_2") (pintype "passive"))
      (node (ref "R20") (pin "1") (pinfunction "1_1") (pintype "passive"))
      (node (ref "U40") (pin "4") (pinfunction "OB_4") (pintype "passive"))
    )
    (net (code "83") (name "VCC") (class "Default")
      (node (ref "C15") (pin "1") (pinfunction "1_1") (pintype "passive"))
      (node (ref "C2") (pin "2") (pinfunction "2_2") (pintype "passive"))
      (node (ref "C20") (pin "1") (pinfunction "1_1") (pintype "passive"))
      (node (ref "C21") (pin "1") (pinfunction "1_1") (pintype "passive"))
      (node (ref "C4") (pin "1") (pinfunction "1_1") (pintype "passive"))
      (node (ref "C5") (pin "1") (pinfunction "1_1") (pintype "passive"))
      (node (ref "C6") (pin "1") (pinfunction "1_1") (pintype "passive"))
      (node (ref "C7") (pin "1") (pinfunction "1_1") (pintype "passive"))
      (node (ref "C8") (pin "1") (pinfunction "1_1") (pintype "passive"))
      (node (ref "C9") (pin "1") (pinfunction "1_1") (pintype "passive"))
      (node (ref "Cx1") (pin "2") (pinfunction "2_2") (pintype "passive"))
      (node (ref "Cx10") (pin "2") (pinfunction "2_2") (pintype "passive"))
      (node (ref "Cx11") (pin "2") (pinfunction "2_2") (pintype "passive"))
      (node (ref "Cx12") (pin "2") (pinfunction "2_2") (pintype "passive"))
      (node (ref "Cx13") (pin "2") (pinfunction "2_2") (pintype "passive"))
      (node (ref "Cx14") (pin "2") (pinfunction "2_2") (pintype "passive"))
      (node (ref "Cx15") (pin "2") (pinfunction "2_2") (pintype "passive"))
      (node (ref "Cx16") (pin "2") (pinfunction "2_2") (pintype "passive"))
      (node (ref "Cx17") (pin "2") (pinfunction "2_2") (pintype "passive"))
      (node (ref "Cx18") (pin "2") (pinfunction "2_2") (pintype "passive"))
      (node (ref "Cx19") (pin "2") (pinfunction "2_2") (pintype "passive"))
      (node (ref "Cx2") (pin "2") (pinfunction "2_2") (pintype "passive"))
      (node (ref "Cx20") (pin "2") (pinfunction "2_2") (pintype "passive"))
      (node (ref "Cx21") (pin "2") (pinfunction "2_2") (pintype "passive"))
      (node (ref "Cx22") (pin "2") (pinfunction "2_2") (pintype "passive"))
      (node (ref "Cx23") (pin "2") (pinfunction "2_2") (pintype "passive"))
      (node (ref "Cx24") (pin "2") (pinfunction "2_2") (pintype "passive"))
      (node (ref "Cx25") (pin "2") (pinfunction "2_2") (pintype "passive"))
      (node (ref "Cx26") (pin "2") (pinfunction "2_2") (pintype "passive"))
      (node (ref "Cx27") (pin "2") (pinfunction "2_2") (pintype "passive"))
      (node (ref "Cx28") (pin "2") (pinfunction "2_2") (pintype "passive"))
      (node (ref "Cx29") (pin "2") (pinfunction "2_2") (pintype "passive"))
      (node (ref "Cx3") (pin "2") (pinfunction "2_2") (pintype "passive"))
      (node (ref "Cx30") (pin "2") (pinfunction "2_2") (pintype "passive"))
      (node (ref "Cx31") (pin "2") (pinfunction "2_2") (pintype "passive"))
      (node (ref "Cx32") (pin "2") (pinfunction "2_2") (pintype "passive"))
      (node (ref "Cx33") (pin "2") (pinfunction "2_2") (pintype "passive"))
      (node (ref "Cx34") (pin "2") (pinfunction "2_2") (pintype "passive"))
      (node (ref "Cx35") (pin "2") (pinfunction "2_2") (pintype "passive"))
      (node (ref "Cx36") (pin "2") (pinfunction "2_2") (pintype "passive"))
      (node (ref "Cx4") (pin "2") (pinfunction "2_2") (pintype "passive"))
      (node (ref "Cx5") (pin "2") (pinfunction "2_2") (pintype "passive"))
      (node (ref "Cx6") (pin "2") (pinfunction "2_2") (pintype "passive"))
      (node (ref "Cx7") (pin "2") (pinfunction "2_2") (pintype "passive"))
      (node (ref "Cx8") (pin "2") (pinfunction "2_2") (pintype "passive"))
      (node (ref "Cx9") (pin "2") (pinfunction "2_2") (pintype "passive"))
      (node (ref "HC1") (pin "5") (pinfunction "VCC_5") (pintype "passive"))
      (node (ref "IC1") (pin "9") (pinfunction "VDD_9") (pintype "passive"))
      (node (ref "R3") (pin "2") (pinfunction "2_2") (pintype "passive"))
      (node (ref "R4") (pin "2") (pinfunction "2_2") (pintype "passive"))
      (node (ref "U1") (pin "1") (pinfunction "VDD_1") (pintype "passive"))
      (node (ref "U10") (pin "1") (pinfunction "VDD_1") (pintype "passive"))
      (node (ref "U11") (pin "1") (pinfunction "VDD_1") (pintype "passive"))
      (node (ref "U12") (pin "1") (pinfunction "VDD_1") (pintype "passive"))
      (node (ref "U13") (pin "1") (pinfunction "VDD_1") (pintype "passive"))
      (node (ref "U14") (pin "1") (pinfunction "VDD_1") (pintype "passive"))
      (node (ref "U15") (pin "1") (pinfunction "VDD_1") (pintype "passive"))
      (node (ref "U16") (pin "1") (pinfunction "VDD_1") (pintype "passive"))
      (node (ref "U17") (pin "1") (pinfunction "VDD_1") (pintype "passive"))
      (node (ref "U18") (pin "1") (pinfunction "VDD_1") (pintype "passive"))
      (node (ref "U19") (pin "1") (pinfunction "VDD_1") (pintype "passive"))
      (node (ref "U2") (pin "1") (pinfunction "VDD_1") (pintype "passive"))
      (node (ref "U20") (pin "1") (pinfunction "VDD_1") (pintype "passive"))
      (node (ref "U21") (pin "1") (pinfunction "VDD_1") (pintype "passive"))
      (node (ref "U22") (pin "1") (pinfunction "VDD_1") (pintype "passive"))
      (node (ref "U23") (pin "1") (pinfunction "VDD_1") (pintype "passive"))
      (node (ref "U24") (pin "1") (pinfunction "VDD_1") (pintype "passive"))
      (node (ref "U26") (pin "1") (pinfunction "VDD_1") (pintype "passive"))
      (node (ref "U27") (pin "1") (pinfunction "VDD_1") (pintype "passive"))
      (node (ref "U28") (pin "1") (pinfunction "VDD_1") (pintype "passive"))
      (node (ref "U29") (pin "1") (pinfunction "VDD_1") (pintype "passive"))
      (node (ref "U3") (pin "1") (pinfunction "VDD_1") (pintype "passive"))
      (node (ref "U30") (pin "1") (pinfunction "VDD_1") (pintype "passive"))
      (node (ref "U31") (pin "1") (pinfunction "VDD_1") (pintype "passive"))
      (node (ref "U33") (pin "1") (pinfunction "VDD_1") (pintype "passive"))
      (node (ref "U34") (pin "1") (pinfunction "VDD_1") (pintype "passive"))
      (node (ref "U35") (pin "1") (pinfunction "VDD_1") (pintype "passive"))
      (node (ref "U36") (pin "1") (pinfunction "VDD_1") (pintype "passive"))
      (node (ref "U38") (pin "1") (pinfunction "VDD_1") (pintype "passive"))
      (node (ref "U39") (pin "1") (pinfunction "VDD_1") (pintype "passive"))
      (node (ref "U4") (pin "1") (pinfunction "VDD_1") (pintype "passive"))
      (node (ref "U5") (pin "1") (pinfunction "VDD_1") (pintype "passive"))
      (node (ref "U6") (pin "1") (pinfunction "VDD_1") (pintype "passive"))
      (node (ref "U7") (pin "1") (pinfunction "VDD_1") (pintype "passive"))
      (node (ref "U8") (pin "1") (pinfunction "VDD_1") (pintype "passive"))
      (node (ref "U9") (pin "1") (pinfunction "VDD_1") (pintype "passive"))
    )
    (net (code "84") (name "unconnected-(HC1-EN-Pad6)") (class "Default")
      (node (ref "HC1") (pin "6") (pinfunction "EN_6") (pintype "passive+no_connect"))
    )
    (net (code "85") (name "unconnected-(HC1-STAT-Pad1)") (class "Default")
      (node (ref "HC1") (pin "1") (pinfunction "STAT_1") (pintype "passive+no_connect"))
    )
    (net (code "86") (name "unconnected-(IC1-PC5(HS){slash}SPI_SCK[TIME2_CH1]-Pad15)") (class "Default")
      (node (ref "IC1") (pin "15") (pinfunction "PC5(HS)/SPI_SCK[TIME2_CH1]_15") (pintype "passive+no_connect"))
    )
    (net (code "87") (name "unconnected-(IC1-PC6(HS){slash}SPI_MOSI[TIM1_CH1]-Pad16)") (class "Default")
      (node (ref "IC1") (pin "16") (pinfunction "PC6(HS)/SPI_MOSI[TIM1_CH1]_16") (pintype "passive+no_connect"))
    )
    (net (code "88") (name "unconnected-(IC1-PC7(HS){slash}SPI_MISO[TIM1_CH2]-Pad17)") (class "Default")
      (node (ref "IC1") (pin "17") (pinfunction "PC7(HS)/SPI_MISO[TIM1_CH2]_17") (pintype "passive+no_connect"))
    )
    (net (code "89") (name "unconnected-(U31-DOUT-Pad2)") (class "Default")
      (node (ref "U31") (pin "2") (pinfunction "DOUT_2") (pintype "passive"))
    )
  )
)
